# stlink-to-bc.net
KiCad netlist of a schematic drawn in EAGLE
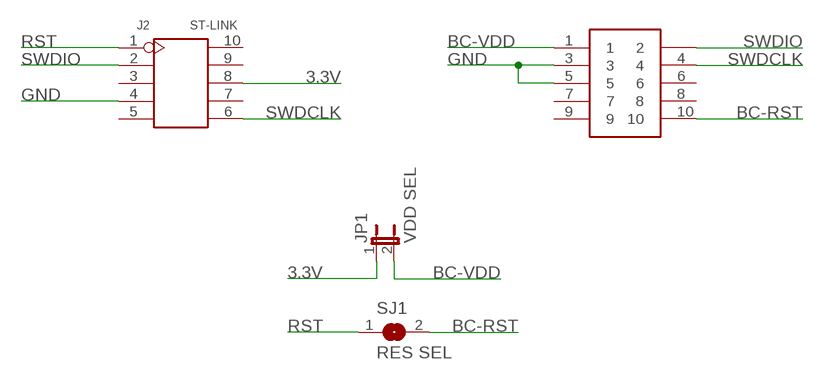
[diagram p0: schematic, sheet 1]

(export (version "E")
  (design (tool "Eeschema 10.0.6"))
  (components
    (comp (ref "J1")
      (value "BC")
      (footprint "eagle-import:SHF105DSM_1")
      (libsource (lib "eagle-import") (part "SHF105"))
    )
    (comp (ref "J2")
      (value "ST-LINK")
      (footprint "eagle-import:V2X5-2.54")
      (libsource (lib "eagle-import") (part "DIP-BLACK-FEMALE-HEADER(2X5P-2.54)V2X5-2.54"))
    )
    (comp (ref "JP1")
      (value "VDD SEL")
      (footprint "eagle-import:JP1")
      (libsource (lib "eagle-import") (part "JP1E"))
    )
    (comp (ref "SJ1")
      (value "RES SEL")
      (footprint "eagle-import:SJ")
      (libsource (lib "eagle-import") (part "SJ"))
    )
  )
  (nets
    (net (code "1") (name "/3.3V") (class "Default")
      (node (ref "J2") (pin "8") (pinfunction "8_8") (pintype "bidirectional"))
      (node (ref "JP1") (pin "1") (pinfunction "1_1") (pintype "passive"))
    )
    (net (code "2") (name "/BC-RST") (class "Default")
      (node (ref "J1") (pin "10") (pinfunction "10_10") (pintype "passive"))
      (node (ref "SJ1") (pin "2") (pinfunction "2_2") (pintype "passive"))
    )
    (net (code "3") (name "/BC-VDD") (class "Default")
      (node (ref "J1") (pin "1") (pinfunction "1_1") (pintype "passive"))
      (node (ref "JP1") (pin "2") (pinfunction "2_2") (pintype "passive"))
    )
    (net (code "4") (name "/GND") (class "Default")
      (node (ref "J1") (pin "3") (pinfunction "3_3") (pintype "passive"))
      (node (ref "J1") (pin "5") (pinfunction "5_5") (pintype "passive"))
      (node (ref "J2") (pin "4") (pinfunction "4_4") (pintype "bidirectional"))
    )
    (net (code "5") (name "/RST") (class "Default")
      (node (ref "J2") (pin "1") (pinfunction "1_1") (pintype "bidirectional"))
      (node (ref "SJ1") (pin "1") (pinfunction "1_1") (pintype "passive"))
    )
    (net (code "6") (name "/SWDCLK") (class "Default")
      (node (ref "J1") (pin "4") (pinfunction "4_4") (pintype "passive"))
      (node (ref "J2") (pin "6") (pinfunction "6_6") (pintype "bidirectional"))
    )
    (net (code "7") (name "/SWDIO") (class "Default")
      (node (ref "J1") (pin "2") (pinfunction "2_2") (pintype "passive"))
      (node (ref "J2") (pin "2") (pinfunction "2_2") (pintype "bidirectional"))
    )
    (net (code "8") (name "unconnected-(J1-Pad6)") (class "Default")
      (node (ref "J1") (pin "6") (pinfunction "6_6") (pintype "passive"))
    )
    (net (code "9") (name "unconnected-(J1-Pad7)") (class "Default")
      (node (ref "J1") (pin "7") (pinfunction "7_7") (pintype "passive"))
    )
    (net (code "10") (name "unconnected-(J1-Pad8)") (class "Default")
      (node (ref "J1") (pin "8") (pinfunction "8_8") (pintype "passive"))
    )
    (net (code "11") (name "unconnected-(J1-Pad9)") (class "Default")
      (node (ref "J1") (pin "9") (pinfunction "9_9") (pintype "passive"))
    )
    (net (code "12") (name "unconnected-(J2-Pad3)") (class "Default")
      (node (ref "J2") (pin "3") (pinfunction "3_3") (pintype "bidirectional"))
    )
    (net (code "13") (name "unconnected-(J2-Pad5)") (class "Default")
      (node (ref "J2") (pin "5") (pinfunction "5_5") (pintype "bidirectional"))
    )
    (net (code "14") (name "unconnected-(J2-Pad7)") (class "Default")
      (node (ref "J2") (pin "7") (pinfunction "7_7") (pintype "bidirectional"))
    )
    (net (code "15") (name "unconnected-(J2-Pad9)") (class "Default")
      (node (ref "J2") (pin "9") (pinfunction "9_9") (pintype "bidirectional"))
    )
    (net (code "16") (name "unconnected-(J2-Pad10)") (class "Default")
      (node (ref "J2") (pin "10") (pinfunction "10_10") (pintype "bidirectional"))
    )
  )
)
